# 6.net
KiCad netlist of a schematic drawn in Altium Designer
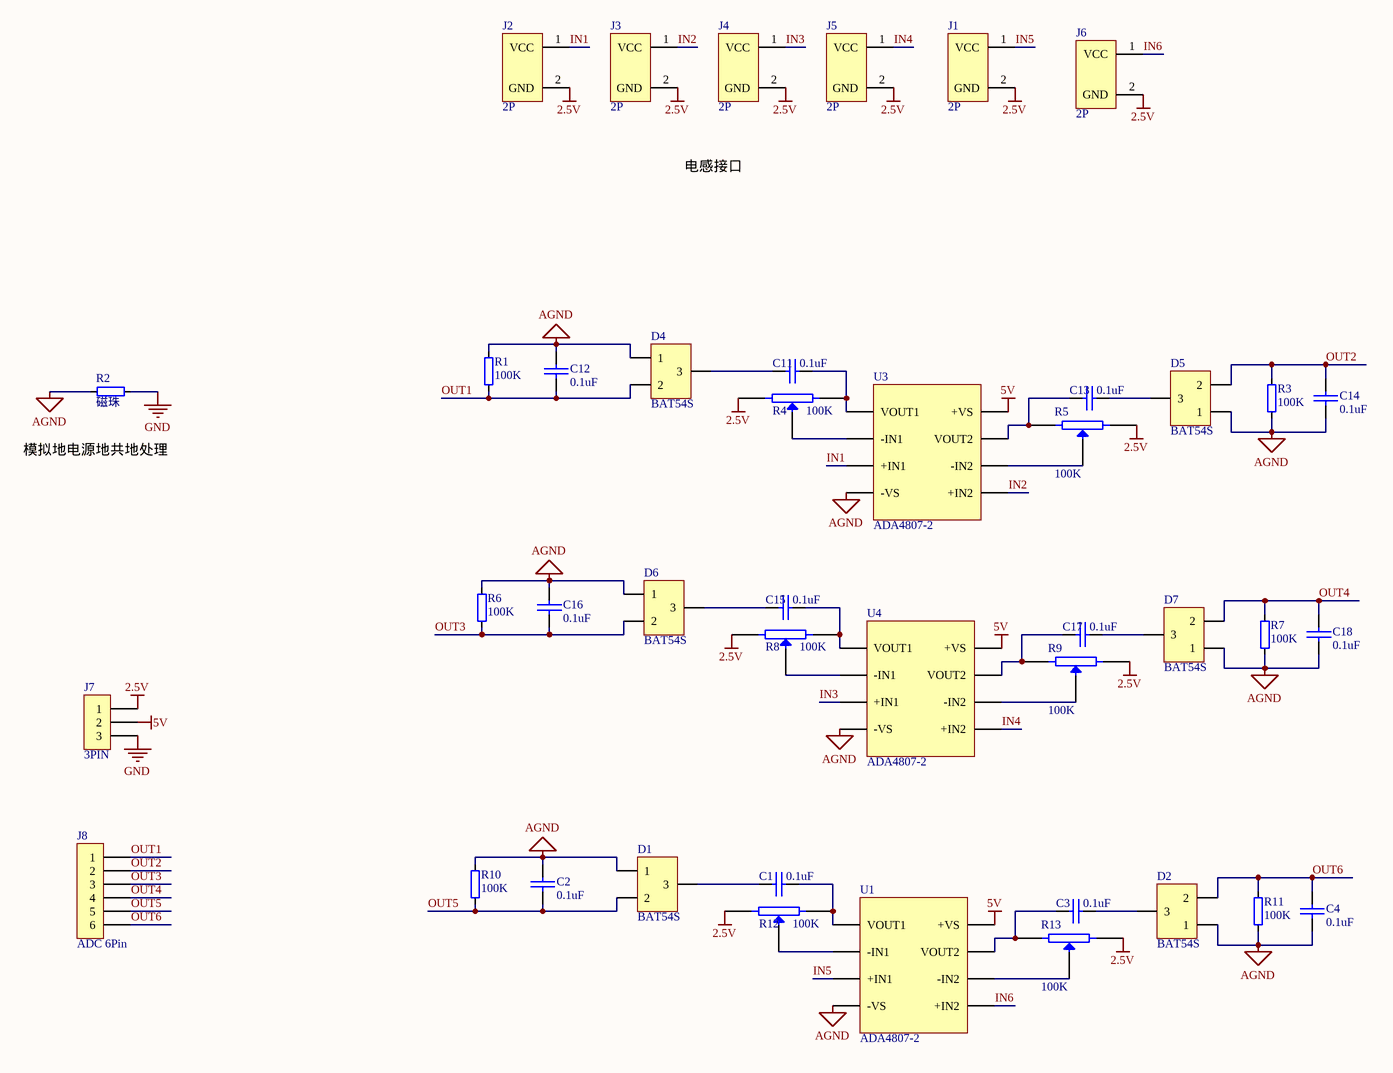
[diagram p0: 6路电磁.SchDoc]

(export (version "E")
  (design (tool "Eeschema 10.0.6"))
  (components
    (comp (ref "C1") (value "0.1uF") (footprint "C0603") (libsource (lib "PowerControl_v1") (part "MLCC")))
    (comp (ref "C2") (value "0.1uF") (footprint "C0603") (libsource (lib "PowerControl_v1") (part "MLCC")))
    (comp (ref "C3") (value "0.1uF") (footprint "C0603") (libsource (lib "PowerControl_v1") (part "MLCC")))
    (comp (ref "C4") (value "0.1uF") (footprint "C0603") (libsource (lib "PowerControl_v1") (part "MLCC")))
    (comp (ref "C11") (value "0.1uF") (footprint "C0603") (libsource (lib "PowerControl_v1") (part "MLCC")))
    (comp (ref "C12") (value "0.1uF") (footprint "C0603") (libsource (lib "PowerControl_v1") (part "MLCC")))
    (comp (ref "C13") (value "0.1uF") (footprint "C0603") (libsource (lib "PowerControl_v1") (part "MLCC")))
    (comp (ref "C14") (value "0.1uF") (footprint "C0603") (libsource (lib "PowerControl_v1") (part "MLCC")))
    (comp (ref "C15") (value "0.1uF") (footprint "C0603") (libsource (lib "PowerControl_v1") (part "MLCC")))
    (comp (ref "C16") (value "0.1uF") (footprint "C0603") (libsource (lib "PowerControl_v1") (part "MLCC")))
    (comp (ref "C17") (value "0.1uF") (footprint "C0603") (libsource (lib "PowerControl_v1") (part "MLCC")))
    (comp (ref "C18") (value "0.1uF") (footprint "C0603") (libsource (lib "PowerControl_v1") (part "MLCC")))
    (comp (ref "D1")
      (value "BAT54S")
      (footprint "SOT-23")
      (libsource (lib "PowerControl_v1") (part "BAT54S"))
    )
    (comp (ref "D2") (value "BAT54S") (footprint "SOT-23") (libsource (lib "") (part "BAT54S_1")))
    (comp (ref "D4")
      (value "BAT54S")
      (footprint "SOT-23")
      (libsource (lib "PowerControl_v1") (part "BAT54S"))
    )
    (comp (ref "D5") (value "BAT54S") (footprint "SOT-23") (libsource (lib "") (part "BAT54S_1")))
    (comp (ref "D6")
      (value "BAT54S")
      (footprint "SOT-23")
      (libsource (lib "PowerControl_v1") (part "BAT54S"))
    )
    (comp (ref "D7") (value "BAT54S") (footprint "SOT-23") (libsource (lib "") (part "BAT54S_1")))
    (comp (ref "J1") (value "2P") (footprint "Header-2pin") (libsource (lib "PowerControl_v1") (part "2P")))
    (comp (ref "J2") (value "2P") (footprint "Header-2pin") (libsource (lib "PowerControl_v1") (part "2P")))
    (comp (ref "J3") (value "2P") (footprint "Header-2pin") (libsource (lib "PowerControl_v1") (part "2P")))
    (comp (ref "J4") (value "2P") (footprint "Header-2pin") (libsource (lib "PowerControl_v1") (part "2P")))
    (comp (ref "J5") (value "2P") (footprint "Header-2pin") (libsource (lib "PowerControl_v1") (part "2P")))
    (comp (ref "J6") (value "2P") (footprint "Header-2pin") (libsource (lib "PowerControl_v1") (part "2P")))
    (comp (ref "J7") (value "3PIN") (footprint "3PIN") (libsource (lib "PowerControl_v1") (part "3PIN")))
    (comp (ref "J8")
      (value "ADC 6Pin")
      (footprint "ADC 6Pin")
      (libsource (lib "PowerControl_v1") (part "ADC 6Pin"))
    )
    (comp (ref "R1") (value "100K") (footprint "R0603") (libsource (lib "PowerControl_v1") (part "RES")))
    (comp (ref "R2") (value "磁珠") (footprint "R0603") (libsource (lib "PowerControl_v1") (part "RES")))
    (comp (ref "R3") (value "100K") (footprint "R0603") (libsource (lib "PowerControl_v1") (part "RES")))
    (comp (ref "R4") (value "100K") (footprint "电位器") (libsource (lib "PowerControl_v1") (part "可调电阻")))
    (comp (ref "R5") (value "100K") (footprint "电位器") (libsource (lib "PowerControl_v1") (part "可调电阻")))
    (comp (ref "R6") (value "100K") (footprint "R0603") (libsource (lib "PowerControl_v1") (part "RES")))
    (comp (ref "R7") (value "100K") (footprint "R0603") (libsource (lib "PowerControl_v1") (part "RES")))
    (comp (ref "R8") (value "100K") (footprint "电位器") (libsource (lib "PowerControl_v1") (part "可调电阻")))
    (comp (ref "R9") (value "100K") (footprint "电位器") (libsource (lib "PowerControl_v1") (part "可调电阻")))
    (comp (ref "R10") (value "100K") (footprint "R0603") (libsource (lib "PowerControl_v1") (part "RES")))
    (comp (ref "R11") (value "100K") (footprint "R0603") (libsource (lib "PowerControl_v1") (part "RES")))
    (comp (ref "R12") (value "100K") (footprint "电位器") (libsource (lib "PowerControl_v1") (part "可调电阻")))
    (comp (ref "R13") (value "100K") (footprint "电位器") (libsource (lib "PowerControl_v1") (part "可调电阻")))
    (comp (ref "U1")
      (value "ADA4807-2")
      (footprint "AD8217")
      (libsource (lib "PowerControl_v1") (part "ADA4807-2"))
    )
    (comp (ref "U3")
      (value "ADA4807-2")
      (footprint "AD8217")
      (libsource (lib "PowerControl_v1") (part "ADA4807-2"))
    )
    (comp (ref "U4")
      (value "ADA4807-2")
      (footprint "AD8217")
      (libsource (lib "PowerControl_v1") (part "ADA4807-2"))
    )
  )
  (nets
    (net (code "1") (name "/IN1") (class "Default")
      (node (ref "J2") (pin "1") (pinfunction "VCC_1") (pintype "passive"))
      (node (ref "U3") (pin "3") (pinfunction "+IN1_3") (pintype "passive"))
    )
    (net (code "2") (name "/IN2") (class "Default")
      (node (ref "J3") (pin "1") (pinfunction "VCC_1") (pintype "passive"))
      (node (ref "U3") (pin "5") (pinfunction "+IN2_5") (pintype "passive"))
    )
    (net (code "3") (name "/IN3") (class "Default")
      (node (ref "J4") (pin "1") (pinfunction "VCC_1") (pintype "passive"))
      (node (ref "U4") (pin "3") (pinfunction "+IN1_3") (pintype "passive"))
    )
    (net (code "4") (name "/IN4") (class "Default")
      (node (ref "J5") (pin "1") (pinfunction "VCC_1") (pintype "passive"))
      (node (ref "U4") (pin "5") (pinfunction "+IN2_5") (pintype "passive"))
    )
    (net (code "5") (name "/IN5") (class "Default")
      (node (ref "J1") (pin "1") (pinfunction "VCC_1") (pintype "passive"))
      (node (ref "U1") (pin "3") (pinfunction "+IN1_3") (pintype "passive"))
    )
    (net (code "6") (name "/IN6") (class "Default")
      (node (ref "J6") (pin "1") (pinfunction "VCC_1") (pintype "passive"))
      (node (ref "U1") (pin "5") (pinfunction "+IN2_5") (pintype "passive"))
    )
    (net (code "7") (name "/OUT1") (class "Default")
      (node (ref "C12") (pin "2") (pinfunction "2_2") (pintype "passive"))
      (node (ref "D4") (pin "2") (pinfunction "2_2") (pintype "passive"))
      (node (ref "J8") (pin "1") (pinfunction "1_1") (pintype "passive"))
      (node (ref "R1") (pin "1") (pinfunction "1_1") (pintype "passive"))
    )
    (net (code "8") (name "/OUT2") (class "Default")
      (node (ref "C14") (pin "1") (pinfunction "1_1") (pintype "passive"))
      (node (ref "D5") (pin "2") (pinfunction "2_2") (pintype "passive"))
      (node (ref "J8") (pin "2") (pinfunction "2_2") (pintype "passive"))
      (node (ref "R3") (pin "2") (pinfunction "2_2") (pintype "passive"))
    )
    (net (code "9") (name "/OUT3") (class "Default")
      (node (ref "C16") (pin "2") (pinfunction "2_2") (pintype "passive"))
      (node (ref "D6") (pin "2") (pinfunction "2_2") (pintype "passive"))
      (node (ref "J8") (pin "3") (pinfunction "3_3") (pintype "passive"))
      (node (ref "R6") (pin "1") (pinfunction "1_1") (pintype "passive"))
    )
    (net (code "10") (name "/OUT4") (class "Default")
      (node (ref "C18") (pin "1") (pinfunction "1_1") (pintype "passive"))
      (node (ref "D7") (pin "2") (pinfunction "2_2") (pintype "passive"))
      (node (ref "J8") (pin "4") (pinfunction "4_4") (pintype "passive"))
      (node (ref "R7") (pin "2") (pinfunction "2_2") (pintype "passive"))
    )
    (net (code "11") (name "/OUT5") (class "Default")
      (node (ref "C2") (pin "2") (pinfunction "2_2") (pintype "passive"))
      (node (ref "D1") (pin "2") (pinfunction "2_2") (pintype "passive"))
      (node (ref "J8") (pin "5") (pinfunction "5_5") (pintype "passive"))
      (node (ref "R10") (pin "1") (pinfunction "1_1") (pintype "passive"))
    )
    (net (code "12") (name "/OUT6") (class "Default")
      (node (ref "C4") (pin "1") (pinfunction "1_1") (pintype "passive"))
      (node (ref "D2") (pin "2") (pinfunction "2_2") (pintype "passive"))
      (node (ref "J8") (pin "6") (pinfunction "6_6") (pintype "passive"))
      (node (ref "R11") (pin "2") (pinfunction "2_2") (pintype "passive"))
    )
    (net (code "13") (name "2.5V") (class "Default")
      (node (ref "J1") (pin "2") (pinfunction "GND_2") (pintype "passive"))
      (node (ref "J2") (pin "2") (pinfunction "GND_2") (pintype "passive"))
      (node (ref "J3") (pin "2") (pinfunction "GND_2") (pintype "passive"))
      (node (ref "J4") (pin "2") (pinfunction "GND_2") (pintype "passive"))
      (node (ref "J5") (pin "2") (pinfunction "GND_2") (pintype "passive"))
      (node (ref "J6") (pin "2") (pinfunction "GND_2") (pintype "passive"))
      (node (ref "J7") (pin "1") (pinfunction "1_1") (pintype "passive"))
      (node (ref "R12") (pin "3") (pinfunction "3_3") (pintype "passive"))
      (node (ref "R13") (pin "1") (pinfunction "1_1") (pintype "passive"))
      (node (ref "R4") (pin "3") (pinfunction "3_3") (pintype "passive"))
      (node (ref "R5") (pin "1") (pinfunction "1_1") (pintype "passive"))
      (node (ref "R8") (pin "3") (pinfunction "3_3") (pintype "passive"))
      (node (ref "R9") (pin "1") (pinfunction "1_1") (pintype "passive"))
    )
    (net (code "14") (name "5V") (class "Default")
      (node (ref "J7") (pin "2") (pinfunction "2_2") (pintype "passive"))
      (node (ref "U1") (pin "8") (pinfunction "+VS_8") (pintype "passive"))
      (node (ref "U3") (pin "8") (pinfunction "+VS_8") (pintype "passive"))
      (node (ref "U4") (pin "8") (pinfunction "+VS_8") (pintype "passive"))
    )
    (net (code "15") (name "AGND") (class "Default")
      (node (ref "C12") (pin "1") (pinfunction "1_1") (pintype "passive"))
      (node (ref "C14") (pin "2") (pinfunction "2_2") (pintype "passive"))
      (node (ref "C16") (pin "1") (pinfunction "1_1") (pintype "passive"))
      (node (ref "C18") (pin "2") (pinfunction "2_2") (pintype "passive"))
      (node (ref "C2") (pin "1") (pinfunction "1_1") (pintype "passive"))
      (node (ref "C4") (pin "2") (pinfunction "2_2") (pintype "passive"))
      (node (ref "D1") (pin "1") (pinfunction "1_1") (pintype "passive"))
      (node (ref "D2") (pin "1") (pinfunction "1_1") (pintype "passive"))
      (node (ref "D4") (pin "1") (pinfunction "1_1") (pintype "passive"))
      (node (ref "D5") (pin "1") (pinfunction "1_1") (pintype "passive"))
      (node (ref "D6") (pin "1") (pinfunction "1_1") (pintype "passive"))
      (node (ref "D7") (pin "1") (pinfunction "1_1") (pintype "passive"))
      (node (ref "R1") (pin "2") (pinfunction "2_2") (pintype "passive"))
      (node (ref "R10") (pin "2") (pinfunction "2_2") (pintype "passive"))
      (node (ref "R11") (pin "1") (pinfunction "1_1") (pintype "passive"))
      (node (ref "R2") (pin "1") (pinfunction "1_1") (pintype "passive"))
      (node (ref "R3") (pin "1") (pinfunction "1_1") (pintype "passive"))
      (node (ref "R6") (pin "2") (pinfunction "2_2") (pintype "passive"))
      (node (ref "R7") (pin "1") (pinfunction "1_1") (pintype "passive"))
      (node (ref "U1") (pin "4") (pinfunction "-VS_4") (pintype "passive"))
      (node (ref "U3") (pin "4") (pinfunction "-VS_4") (pintype "passive"))
      (node (ref "U4") (pin "4") (pinfunction "-VS_4") (pintype "passive"))
    )
    (net (code "16") (name "GND") (class "Default")
      (node (ref "J7") (pin "3") (pinfunction "3_3") (pintype "passive"))
      (node (ref "R2") (pin "2") (pinfunction "2_2") (pintype "passive"))
    )
    (net (code "17") (name "Net-(C1-Pad1)") (class "Default")
      (node (ref "C1") (pin "1") (pinfunction "1_1") (pintype "passive"))
      (node (ref "D1") (pin "3") (pinfunction "3_3") (pintype "passive"))
    )
    (net (code "18") (name "Net-(C3-Pad2)") (class "Default")
      (node (ref "C3") (pin "2") (pinfunction "2_2") (pintype "passive"))
      (node (ref "D2") (pin "3") (pinfunction "3_3") (pintype "passive"))
    )
    (net (code "19") (name "Net-(C11-Pad1)") (class "Default")
      (node (ref "C11") (pin "1") (pinfunction "1_1") (pintype "passive"))
      (node (ref "D4") (pin "3") (pinfunction "3_3") (pintype "passive"))
    )
    (net (code "20") (name "Net-(C13-Pad2)") (class "Default")
      (node (ref "C13") (pin "2") (pinfunction "2_2") (pintype "passive"))
      (node (ref "D5") (pin "3") (pinfunction "3_3") (pintype "passive"))
    )
    (net (code "21") (name "Net-(C15-Pad1)") (class "Default")
      (node (ref "C15") (pin "1") (pinfunction "1_1") (pintype "passive"))
      (node (ref "D6") (pin "3") (pinfunction "3_3") (pintype "passive"))
    )
    (net (code "22") (name "Net-(C17-Pad2)") (class "Default")
      (node (ref "C17") (pin "2") (pinfunction "2_2") (pintype "passive"))
      (node (ref "D7") (pin "3") (pinfunction "3_3") (pintype "passive"))
    )
    (net (code "23") (name "Net-(R4-W)") (class "Default")
      (node (ref "R4") (pin "2") (pinfunction "W_2") (pintype "passive"))
      (node (ref "U3") (pin "2") (pinfunction "-IN1_2") (pintype "passive"))
    )
    (net (code "24") (name "Net-(R5-W)") (class "Default")
      (node (ref "R5") (pin "2") (pinfunction "W_2") (pintype "passive"))
      (node (ref "U3") (pin "6") (pinfunction "-IN2_6") (pintype "passive"))
    )
    (net (code "25") (name "Net-(R8-W)") (class "Default")
      (node (ref "R8") (pin "2") (pinfunction "W_2") (pintype "passive"))
      (node (ref "U4") (pin "2") (pinfunction "-IN1_2") (pintype "passive"))
    )
    (net (code "26") (name "Net-(R9-W)") (class "Default")
      (node (ref "R9") (pin "2") (pinfunction "W_2") (pintype "passive"))
      (node (ref "U4") (pin "6") (pinfunction "-IN2_6") (pintype "passive"))
    )
    (net (code "27") (name "Net-(R12-W)") (class "Default")
      (node (ref "R12") (pin "2") (pinfunction "W_2") (pintype "passive"))
      (node (ref "U1") (pin "2") (pinfunction "-IN1_2") (pintype "passive"))
    )
    (net (code "28") (name "Net-(R13-W)") (class "Default")
      (node (ref "R13") (pin "2") (pinfunction "W_2") (pintype "passive"))
      (node (ref "U1") (pin "6") (pinfunction "-IN2_6") (pintype "passive"))
    )
    (net (code "29") (name "Net-(U1-VOUT1)") (class "Default")
      (node (ref "C1") (pin "2") (pinfunction "2_2") (pintype "passive"))
      (node (ref "R12") (pin "1") (pinfunction "1_1") (pintype "passive"))
      (node (ref "U1") (pin "1") (pinfunction "VOUT1_1") (pintype "passive"))
    )
    (net (code "30") (name "Net-(U1-VOUT2)") (class "Default")
      (node (ref "C3") (pin "1") (pinfunction "1_1") (pintype "passive"))
      (node (ref "R13") (pin "3") (pinfunction "3_3") (pintype "passive"))
      (node (ref "U1") (pin "7") (pinfunction "VOUT2_7") (pintype "passive"))
    )
    (net (code "31") (name "Net-(U3-VOUT1)") (class "Default")
      (node (ref "C11") (pin "2") (pinfunction "2_2") (pintype "passive"))
      (node (ref "R4") (pin "1") (pinfunction "1_1") (pintype "passive"))
      (node (ref "U3") (pin "1") (pinfunction "VOUT1_1") (pintype "passive"))
    )
    (net (code "32") (name "Net-(U3-VOUT2)") (class "Default")
      (node (ref "C13") (pin "1") (pinfunction "1_1") (pintype "passive"))
      (node (ref "R5") (pin "3") (pinfunction "3_3") (pintype "passive"))
      (node (ref "U3") (pin "7") (pinfunction "VOUT2_7") (pintype "passive"))
    )
    (net (code "33") (name "Net-(U4-VOUT1)") (class "Default")
      (node (ref "C15") (pin "2") (pinfunction "2_2") (pintype "passive"))
      (node (ref "R8") (pin "1") (pinfunction "1_1") (pintype "passive"))
      (node (ref "U4") (pin "1") (pinfunction "VOUT1_1") (pintype "passive"))
    )
    (net (code "34") (name "Net-(U4-VOUT2)") (class "Default")
      (node (ref "C17") (pin "1") (pinfunction "1_1") (pintype "passive"))
      (node (ref "R9") (pin "3") (pinfunction "3_3") (pintype "passive"))
      (node (ref "U4") (pin "7") (pinfunction "VOUT2_7") (pintype "passive"))
    )
  )
)
